# target_connectors.net
KiCad netlist of a schematic drawn in Altium Designer
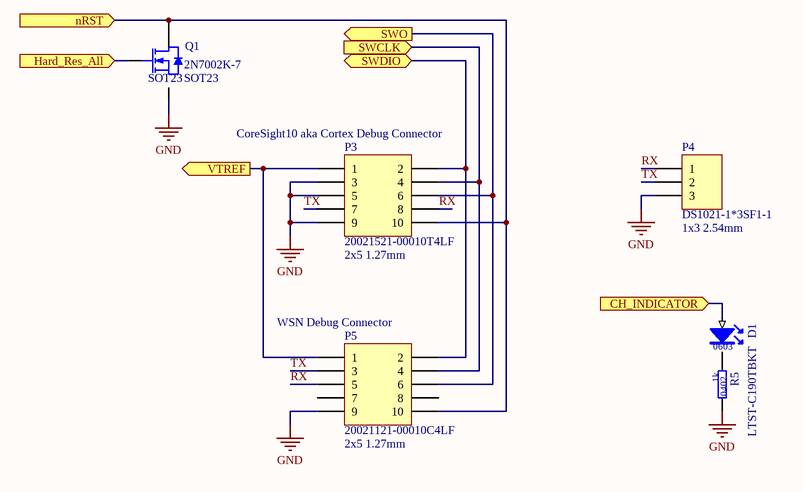
[diagram p0: target_connectors.SchDoc]

(export (version "E")
  (design (tool "Eeschema 10.0.6"))
  (components
    (comp (ref "D1")
      (value "LTST-C190TBKT")
      (footprint "OL_0603_1608")
      (description "LED_BLUE")
      (fields
        (field (name "SCH_FOOTPRINT") "0603")
        (field (name "PART NUMBER") "OL_B_0603")
        (field (name "MANUFACTURER") "Lite-On")
      )
      (libsource (lib "Library") (part "OL_B"))
    )
    (comp (ref "P3")
      (value "20021521-00010T4LF")
      (footprint "P_IDC_2x5_1.27")
      (description "Header, 10-Pin, Dual row")
      (fields
        (field (name "PART NUMBER") "P_IDC_2x5_1.27")
        (field (name "SCH_FOOTPRINT") "2x5 1.27mm")
        (field (name "MANUFACTURER") "Amphenol")
      )
      (libsource (lib "Library") (part "P_HEADER_2x5"))
    )
    (comp (ref "P4")
      (value "DS1021-1*3SF1-1")
      (footprint "P_HEADER_1x3_2.54")
      (description "Header, 3-Pin")
      (fields
        (field (name "PART NUMBER") "P_HEADER_1x3_2.54")
        (field (name "SCH_FOOTPRINT") "1x3 2.54mm")
        (field (name "MANUFACTURER") "Connfly")
      )
      (libsource (lib "Library") (part "P_HEADER_1x3"))
    )
    (comp (ref "P5")
      (value "20021121-00010C4LF")
      (footprint "P_HEADER_2x5_1.27")
      (description "Header, 10-Pin, Dual row")
      (fields
        (field (name "PART NUMBER") "P_HEADER_2x5_1.27")
        (field (name "SCH_FOOTPRINT") "2x5 1.27mm")
        (field (name "MANUFACTURER") "FCI")
      )
      (libsource (lib "Library") (part "P_HEADER_2x5"))
    )
    (comp (ref "Q1")
      (value "2N7002K-7")
      (footprint "SOT23_TO236_SC59")
      (fields
        (field (name "PART NUMBER") "QN_2N7002K-7_60V_350mA")
        (field (name "SCH_FOOTPRINT") "SOT23")
        (field (name "VOLTAGE") "60V")
        (field (name "MANUFACTURER") "DIODES inc")
      )
      (libsource (lib "Library") (part "QN_GSD"))
    )
    (comp (ref "R5")
      (value "1k")
      (footprint "R_0402_1005")
      (fields
        (field (name "SCH_FOOTPRINT") "0402")
        (field (name "PART NUMBER") "R_1k_0402_1")
        (field (name "VOLTAGE") "50V")
        (field (name "POWER") "63mW")
      )
      (libsource (lib "Library") (part "R"))
    )
  )
  (nets
    (net (code "1") (name "/CH_INDICATOR") (class "Default")
      (node (ref "D1") (pin "2") (pinfunction "A_2") (pintype "input"))
    )
    (net (code "2") (name "/Hard_Res_All") (class "Default")
      (node (ref "Q1") (pin "1") (pinfunction "G_1") (pintype "passive"))
    )
    (net (code "3") (name "/RX") (class "Default")
      (node (ref "P3") (pin "8") (pinfunction "8_8") (pintype "passive"))
      (node (ref "P4") (pin "1") (pinfunction "1_1") (pintype "passive"))
      (node (ref "P5") (pin "5") (pinfunction "5_5") (pintype "passive"))
    )
    (net (code "4") (name "/SWCLK") (class "Default")
      (node (ref "P3") (pin "4") (pinfunction "4_4") (pintype "passive"))
      (node (ref "P5") (pin "4") (pinfunction "4_4") (pintype "passive"))
    )
    (net (code "5") (name "/SWDIO") (class "Default")
      (node (ref "P3") (pin "2") (pinfunction "2_2") (pintype "passive"))
      (node (ref "P5") (pin "2") (pinfunction "2_2") (pintype "passive"))
    )
    (net (code "6") (name "/SWO") (class "Default")
      (node (ref "P3") (pin "6") (pinfunction "6_6") (pintype "passive"))
      (node (ref "P5") (pin "6") (pinfunction "6_6") (pintype "passive"))
    )
    (net (code "7") (name "/TX") (class "Default")
      (node (ref "P3") (pin "7") (pinfunction "7_7") (pintype "passive"))
      (node (ref "P4") (pin "2") (pinfunction "2_2") (pintype "passive"))
      (node (ref "P5") (pin "3") (pinfunction "3_3") (pintype "passive"))
    )
    (net (code "8") (name "/VTREF") (class "Default")
      (node (ref "P3") (pin "1") (pinfunction "1_1") (pintype "passive"))
      (node (ref "P5") (pin "1") (pinfunction "1_1") (pintype "passive"))
    )
    (net (code "9") (name "/nRST") (class "Default")
      (node (ref "P3") (pin "10") (pinfunction "10_10") (pintype "passive"))
      (node (ref "P5") (pin "10") (pinfunction "10_10") (pintype "passive"))
      (node (ref "Q1") (pin "3") (pinfunction "D_3") (pintype "passive"))
    )
    (net (code "10") (name "GND") (class "Default")
      (node (ref "P3") (pin "3") (pinfunction "3_3") (pintype "passive"))
      (node (ref "P3") (pin "5") (pinfunction "5_5") (pintype "passive"))
      (node (ref "P3") (pin "9") (pinfunction "9_9") (pintype "passive"))
      (node (ref "P4") (pin "3") (pinfunction "3_3") (pintype "passive"))
      (node (ref "P5") (pin "9") (pinfunction "9_9") (pintype "passive"))
      (node (ref "Q1") (pin "2") (pinfunction "S_2") (pintype "passive"))
      (node (ref "R5") (pin "2") (pinfunction "2_2") (pintype "passive"))
    )
    (net (code "11") (name "Net-(D1-K)") (class "Default")
      (node (ref "D1") (pin "1") (pinfunction "K_1") (pintype "output"))
      (node (ref "R5") (pin "1") (pinfunction "1_1") (pintype "passive"))
    )
    (net (code "12") (name "unconnected-(P5-Pad7)") (class "Default")
      (node (ref "P5") (pin "7") (pinfunction "7_7") (pintype "passive"))
    )
    (net (code "13") (name "unconnected-(P5-Pad8)") (class "Default")
      (node (ref "P5") (pin "8") (pinfunction "8_8") (pintype "passive"))
    )
  )
)
